# MCU.net
KiCad netlist of a schematic drawn in Altium Designer
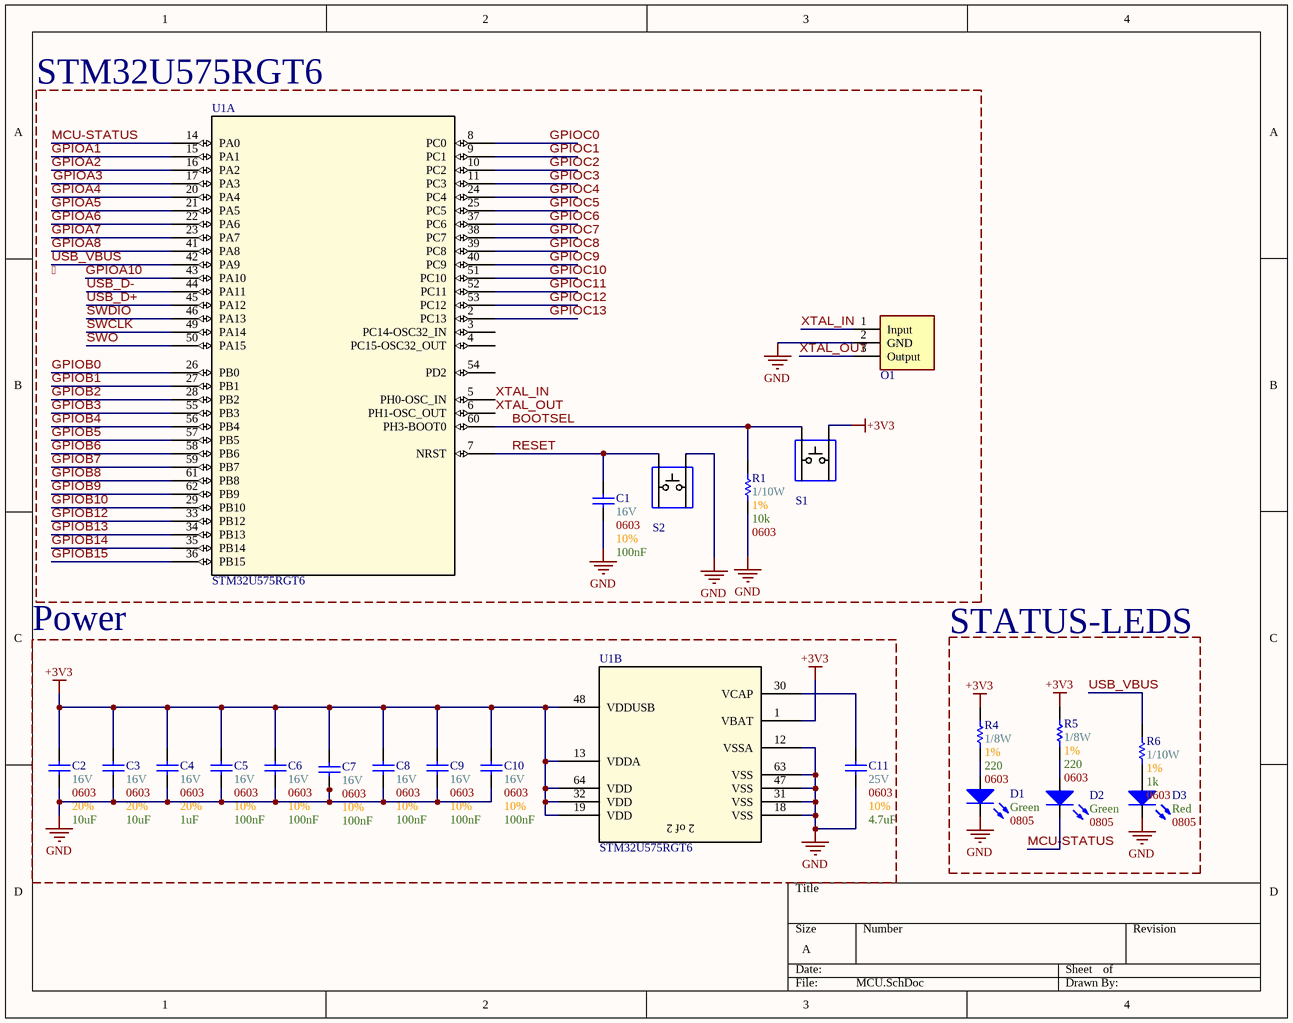
[diagram p0: MCU.SchDoc]

(export (version "E")
  (design (tool "Eeschema 10.0.6"))
  (components
    (comp (ref "C1")
      (value "[Cap] 0603 0.1uF 10% 16V")
      (footprint "[Cap] SMD 0603")
      (description "CC0603KRX7R7BB104")
      (fields
        (field (name "MAX VOLTAGE") "16V")
        (field (name "SIZE PACKAGE") "0603")
        (field (name "TOLERANCE") "10%")
        (field (name "CAPACITANCE") "100nF")
      )
      (libsource (lib "Capacitors") (part "[Cap] 0603 0.1uF 10% 16V"))
    )
    (comp (ref "C2")
      (value "[Cap] 0603 10uF 20% 16V")
      (footprint "[Cap] SMD 0603")
      (description "GRM188C81C106MA73D")
      (fields
        (field (name "MAX VOLTAGE") "16V")
        (field (name "SIZE PACKAGE") "0603")
        (field (name "TOLERANCE") "20%")
        (field (name "CAPACITANCE") "10uF")
      )
      (libsource (lib "Capacitors") (part "[Cap] 0603 10uF 20% 16V"))
    )
    (comp (ref "C3")
      (value "[Cap] 0603 10uF 20% 16V")
      (footprint "[Cap] SMD 0603")
      (description "GRM188C81C106MA73D")
      (fields
        (field (name "MAX VOLTAGE") "16V")
        (field (name "SIZE PACKAGE") "0603")
        (field (name "TOLERANCE") "20%")
        (field (name "CAPACITANCE") "10uF")
      )
      (libsource (lib "Capacitors") (part "[Cap] 0603 10uF 20% 16V"))
    )
    (comp (ref "C4")
      (value "[Cap] 0603 10uF 20% 16V")
      (footprint "[Cap] SMD 0603")
      (description "GRM188C81C106MA73D")
      (fields
        (field (name "MAX VOLTAGE") "16V")
        (field (name "SIZE PACKAGE") "0603")
        (field (name "TOLERANCE") "20%")
        (field (name "CAPACITANCE") "1uF")
      )
      (libsource (lib "Capacitors") (part "[Cap] 0603 10uF 20% 16V"))
    )
    (comp (ref "C5")
      (value "[Cap] 0603 0.1uF 10% 16V")
      (footprint "[Cap] SMD 0603")
      (description "CC0603KRX7R7BB104")
      (fields
        (field (name "MAX VOLTAGE") "16V")
        (field (name "SIZE PACKAGE") "0603")
        (field (name "TOLERANCE") "10%")
        (field (name "CAPACITANCE") "100nF")
      )
      (libsource (lib "Capacitors") (part "[Cap] 0603 0.1uF 10% 16V"))
    )
    (comp (ref "C6")
      (value "[Cap] 0603 0.1uF 10% 16V")
      (footprint "[Cap] SMD 0603")
      (description "CC0603KRX7R7BB104")
      (fields
        (field (name "MAX VOLTAGE") "16V")
        (field (name "SIZE PACKAGE") "0603")
        (field (name "TOLERANCE") "10%")
        (field (name "CAPACITANCE") "100nF")
      )
      (libsource (lib "Capacitors") (part "[Cap] 0603 0.1uF 10% 16V"))
    )
    (comp (ref "C7")
      (value "[Cap] 0603 0.1uF 10% 16V")
      (footprint "[Cap] SMD 0603")
      (description "CC0603KRX7R7BB104")
      (fields
        (field (name "MAX VOLTAGE") "16V")
        (field (name "SIZE PACKAGE") "0603")
        (field (name "TOLERANCE") "10%")
        (field (name "CAPACITANCE") "100nF")
      )
      (libsource (lib "Capacitors") (part "[Cap] 0603 0.1uF 10% 16V"))
    )
    (comp (ref "C8")
      (value "[Cap] 0603 0.1uF 10% 16V")
      (footprint "[Cap] SMD 0603")
      (description "CC0603KRX7R7BB104")
      (fields
        (field (name "MAX VOLTAGE") "16V")
        (field (name "SIZE PACKAGE") "0603")
        (field (name "TOLERANCE") "10%")
        (field (name "CAPACITANCE") "100nF")
      )
      (libsource (lib "Capacitors") (part "[Cap] 0603 0.1uF 10% 16V"))
    )
    (comp (ref "C9")
      (value "[Cap] 0603 0.1uF 10% 16V")
      (footprint "[Cap] SMD 0603")
      (description "CC0603KRX7R7BB104")
      (fields
        (field (name "MAX VOLTAGE") "16V")
        (field (name "SIZE PACKAGE") "0603")
        (field (name "TOLERANCE") "10%")
        (field (name "CAPACITANCE") "100nF")
      )
      (libsource (lib "Capacitors") (part "[Cap] 0603 0.1uF 10% 16V"))
    )
    (comp (ref "C10")
      (value "[Cap] 0603 0.1uF 10% 16V")
      (footprint "[Cap] SMD 0603")
      (description "CC0603KRX7R7BB104")
      (fields
        (field (name "MAX VOLTAGE") "16V")
        (field (name "SIZE PACKAGE") "0603")
        (field (name "TOLERANCE") "10%")
        (field (name "CAPACITANCE") "100nF")
      )
      (libsource (lib "Capacitors") (part "[Cap] 0603 0.1uF 10% 16V"))
    )
    (comp (ref "C11")
      (value "[Cap] 0603 4.7uF 10% 25V")
      (footprint "[Cap] SMD 0603")
      (description "GRM188R61E475KE11D")
      (fields
        (field (name "MAX VOLTAGE") "25V")
        (field (name "SIZE PACKAGE") "0603")
        (field (name "TOLERANCE") "10%")
        (field (name "CAPACITANCE") "4.7uF")
      )
      (libsource (lib "Capacitors") (part "[Cap] 0603 4.7uF 10% 25V"))
    )
    (comp (ref "D1")
      (value "[LED] SMD 0805 Green")
      (footprint "[LED] SMD 0805")
      (description "LG R971-KN-1-0-20-R18")
      (fields (field (name "COLOR") "Green") (field (name "SIZE PACKAGE") "0805"))
      (libsource (lib "LEDs") (part "[LED] SMD 0805 Green"))
    )
    (comp (ref "D2")
      (value "[LED] SMD 0805 Green")
      (footprint "[LED] SMD 0805")
      (description "LG R971-KN-1-0-20-R18")
      (fields (field (name "COLOR") "Green") (field (name "SIZE PACKAGE") "0805"))
      (libsource (lib "LEDs") (part "[LED] SMD 0805 Green"))
    )
    (comp (ref "D3")
      (value "[LED] SMD 0805 Red")
      (footprint "[LED] SMD 0805")
      (description "LS R976-NR-1-0-20-R18")
      (fields (field (name "COLOR") "Red") (field (name "SIZE PACKAGE") "0805"))
      (libsource (lib "LEDs") (part "[LED] SMD 0805 Red"))
    )
    (comp (ref "O1")
      (value "XOSC 12MHz")
      (footprint "[Resonator] SMD 12MHz")
      (description "CSTNE12M0GH5L000R0")
      (libsource (lib "Crystals and Oscillators") (part "[Resonator] SMD 12MHz"))
    )
    (comp (ref "R1")
      (value "[10k] SMD 0603 1% 1/8W")
      (footprint "[Res] SMD 0603")
      (description "RMCF0603FT10K0")
      (fields
        (field (name "WATTAGE") "1/10W")
        (field (name "TOLERANCE") "1%")
        (field (name "RESISTANCE") "10k")
        (field (name "SIZE PACKAGE") "0603")
      )
      (libsource (lib "Resistors") (part "[10k] SMD 0603 1% 1/8W"))
    )
    (comp (ref "R4")
      (value "[220] SMD 0603 1% 1/10W")
      (footprint "[Res] SMD 0603")
      (description "CRGCQ0805F220R")
      (fields
        (field (name "WATTAGE") "1/8W")
        (field (name "TOLERANCE") "1%")
        (field (name "RESISTANCE") "220")
        (field (name "SIZE PACKAGE") "0603")
      )
      (libsource (lib "Resistors") (part "[220] SMD 0603 1% 1/10W"))
    )
    (comp (ref "R5")
      (value "[220] SMD 0603 1% 1/10W")
      (footprint "[Res] SMD 0603")
      (description "CRGCQ0805F220R")
      (fields
        (field (name "WATTAGE") "1/8W")
        (field (name "TOLERANCE") "1%")
        (field (name "RESISTANCE") "220")
        (field (name "SIZE PACKAGE") "0603")
      )
      (libsource (lib "Resistors") (part "[220] SMD 0603 1% 1/10W"))
    )
    (comp (ref "R6")
      (value "[1k] SMD 0603 1% 1/10W")
      (footprint "[Res] SMD 0603")
      (description "RMCF0603FT1K00")
      (fields
        (field (name "WATTAGE") "1/10W")
        (field (name "TOLERANCE") "1%")
        (field (name "RESISTANCE") "1k")
        (field (name "SIZE PACKAGE") "0603")
      )
      (libsource (lib "Resistors") (part "[1k] SMD 0603 1% 1/10W"))
    )
    (comp (ref "S1")
      (value "Standard pushbutton")
      (footprint "[SPST] Pushbutton")
      (libsource (lib "Switches") (part "[SPST] Pushbutton"))
    )
    (comp (ref "S2")
      (value "Standard pushbutton")
      (footprint "[SPST] Pushbutton")
      (libsource (lib "Switches") (part "[SPST] Pushbutton"))
    )
    (comp (ref "U1")
      (value "STM32U575RGT6")
      (footprint "LQFP64-10x10mm_STM")
      (description "Ultra-low-power with FPU Arm Cortex-M33 MCU with TrustZone, 160 MHz with 1 Mbyte of Flash memory")
      (fields (field (name "COPYRIGHT") "Copyright (C) 2025 Ultra Librarian. All rights reserved."))
      (libsource (lib "Solar Gators") (part "STM32U575RGT6"))
    )
  )
  (nets
    (net (code "1") (name "+3V3") (class "Default")
      (node (ref "C10") (pin "2") (pinfunction "2_2") (pintype "passive"))
      (node (ref "C2") (pin "2") (pinfunction "2_2") (pintype "passive"))
      (node (ref "C3") (pin "2") (pinfunction "2_2") (pintype "passive"))
      (node (ref "C4") (pin "2") (pinfunction "2_2") (pintype "passive"))
      (node (ref "C5") (pin "2") (pinfunction "2_2") (pintype "passive"))
      (node (ref "C6") (pin "2") (pinfunction "2_2") (pintype "passive"))
      (node (ref "C7") (pin "2") (pinfunction "2_2") (pintype "passive"))
      (node (ref "C8") (pin "2") (pinfunction "2_2") (pintype "passive"))
      (node (ref "C9") (pin "2") (pinfunction "2_2") (pintype "passive"))
      (node (ref "R4") (pin "2") (pinfunction "2_2") (pintype "passive"))
      (node (ref "R5") (pin "2") (pinfunction "2_2") (pintype "passive"))
      (node (ref "S1") (pin "1") (pintype "power_in"))
      (node (ref "U1") (pin "1") (pinfunction "VBAT_1") (pintype "power_in"))
      (node (ref "U1") (pin "13") (pinfunction "VDDA_13") (pintype "power_in"))
      (node (ref "U1") (pin "19") (pinfunction "VDD_19") (pintype "power_in"))
      (node (ref "U1") (pin "32") (pinfunction "VDD_32") (pintype "power_in"))
      (node (ref "U1") (pin "48") (pinfunction "VDDUSB_48") (pintype "power_in"))
      (node (ref "U1") (pin "64") (pinfunction "VDD_64") (pintype "power_in"))
    )
    (net (code "3") (name "/BOOTSEL") (class "Default")
      (node (ref "R1") (pin "2") (pinfunction "2_2") (pintype "passive"))
      (node (ref "S1") (pin "2") (pintype "power_in"))
      (node (ref "U1") (pin "60") (pinfunction "PH3-BOOT0_60") (pintype "bidirectional"))
    )
    (net (code "4") (name "/GPIOA1") (class "Default")
      (node (ref "U1") (pin "15") (pinfunction "PA1_15") (pintype "bidirectional"))
    )
    (net (code "5") (name "/GPIOA2") (class "Default")
      (node (ref "U1") (pin "16") (pinfunction "PA2_16") (pintype "bidirectional"))
    )
    (net (code "6") (name "/GPIOA3") (class "Default")
      (node (ref "U1") (pin "17") (pinfunction "PA3_17") (pintype "bidirectional"))
    )
    (net (code "7") (name "/GPIOA4") (class "Default")
      (node (ref "U1") (pin "20") (pinfunction "PA4_20") (pintype "bidirectional"))
    )
    (net (code "8") (name "/GPIOA5") (class "Default")
      (node (ref "U1") (pin "21") (pinfunction "PA5_21") (pintype "bidirectional"))
    )
    (net (code "9") (name "/GPIOA6") (class "Default")
      (node (ref "U1") (pin "22") (pinfunction "PA6_22") (pintype "bidirectional"))
    )
    (net (code "10") (name "/GPIOA7") (class "Default")
      (node (ref "U1") (pin "23") (pinfunction "PA7_23") (pintype "bidirectional"))
    )
    (net (code "11") (name "/GPIOA8") (class "Default")
      (node (ref "U1") (pin "41") (pinfunction "PA8_41") (pintype "bidirectional"))
    )
    (net (code "12") (name "/GPIOA10") (class "Default")
      (node (ref "U1") (pin "43") (pinfunction "PA10_43") (pintype "bidirectional"))
    )
    (net (code "13") (name "/GPIOB0") (class "Default")
      (node (ref "U1") (pin "26") (pinfunction "PB0_26") (pintype "bidirectional"))
    )
    (net (code "14") (name "/GPIOB1") (class "Default")
      (node (ref "U1") (pin "27") (pinfunction "PB1_27") (pintype "bidirectional"))
    )
    (net (code "15") (name "/GPIOB2") (class "Default")
      (node (ref "U1") (pin "28") (pinfunction "PB2_28") (pintype "bidirectional"))
    )
    (net (code "16") (name "/GPIOB3") (class "Default")
      (node (ref "U1") (pin "55") (pinfunction "PB3_55") (pintype "bidirectional"))
    )
    (net (code "17") (name "/GPIOB4") (class "Default")
      (node (ref "U1") (pin "56") (pinfunction "PB4_56") (pintype "bidirectional"))
    )
    (net (code "18") (name "/GPIOB5") (class "Default")
      (node (ref "U1") (pin "57") (pinfunction "PB5_57") (pintype "bidirectional"))
    )
    (net (code "19") (name "/GPIOB6") (class "Default")
      (node (ref "U1") (pin "58") (pinfunction "PB6_58") (pintype "bidirectional"))
    )
    (net (code "20") (name "/GPIOB7") (class "Default")
      (node (ref "U1") (pin "59") (pinfunction "PB7_59") (pintype "bidirectional"))
    )
    (net (code "21") (name "/GPIOB8") (class "Default")
      (node (ref "U1") (pin "61") (pinfunction "PB8_61") (pintype "bidirectional"))
    )
    (net (code "22") (name "/GPIOB9") (class "Default")
      (node (ref "U1") (pin "62") (pinfunction "PB9_62") (pintype "bidirectional"))
    )
    (net (code "23") (name "/GPIOB10") (class "Default")
      (node (ref "U1") (pin "29") (pinfunction "PB10_29") (pintype "bidirectional"))
    )
    (net (code "24") (name "/GPIOB12") (class "Default")
      (node (ref "U1") (pin "33") (pinfunction "PB12_33") (pintype "bidirectional"))
    )
    (net (code "25") (name "/GPIOB13") (class "Default")
      (node (ref "U1") (pin "34") (pinfunction "PB13_34") (pintype "bidirectional"))
    )
    (net (code "26") (name "/GPIOB14") (class "Default")
      (node (ref "U1") (pin "35") (pinfunction "PB14_35") (pintype "bidirectional"))
    )
    (net (code "27") (name "/GPIOB15") (class "Default")
      (node (ref "U1") (pin "36") (pinfunction "PB15_36") (pintype "bidirectional"))
    )
    (net (code "28") (name "/GPIOC0") (class "Default")
      (node (ref "U1") (pin "8") (pinfunction "PC0_8") (pintype "bidirectional"))
    )
    (net (code "29") (name "/GPIOC1") (class "Default")
      (node (ref "U1") (pin "9") (pinfunction "PC1_9") (pintype "bidirectional"))
    )
    (net (code "30") (name "/GPIOC2") (class "Default")
      (node (ref "U1") (pin "10") (pinfunction "PC2_10") (pintype "bidirectional"))
    )
    (net (code "31") (name "/GPIOC3") (class "Default")
      (node (ref "U1") (pin "11") (pinfunction "PC3_11") (pintype "bidirectional"))
    )
    (net (code "32") (name "/GPIOC4") (class "Default")
      (node (ref "U1") (pin "24") (pinfunction "PC4_24") (pintype "bidirectional"))
    )
    (net (code "33") (name "/GPIOC5") (class "Default")
      (node (ref "U1") (pin "25") (pinfunction "PC5_25") (pintype "bidirectional"))
    )
    (net (code "34") (name "/GPIOC6") (class "Default")
      (node (ref "U1") (pin "37") (pinfunction "PC6_37") (pintype "bidirectional"))
    )
    (net (code "35") (name "/GPIOC7") (class "Default")
      (node (ref "U1") (pin "38") (pinfunction "PC7_38") (pintype "bidirectional"))
    )
    (net (code "36") (name "/GPIOC8") (class "Default")
      (node (ref "U1") (pin "39") (pinfunction "PC8_39") (pintype "bidirectional"))
    )
    (net (code "37") (name "/GPIOC9") (class "Default")
      (node (ref "U1") (pin "40") (pinfunction "PC9_40") (pintype "bidirectional"))
    )
    (net (code "38") (name "/GPIOC10") (class "Default")
      (node (ref "U1") (pin "51") (pinfunction "PC10_51") (pintype "bidirectional"))
    )
    (net (code "39") (name "/GPIOC11") (class "Default")
      (node (ref "U1") (pin "52") (pinfunction "PC11_52") (pintype "bidirectional"))
    )
    (net (code "40") (name "/GPIOC12") (class "Default")
      (node (ref "U1") (pin "53") (pinfunction "PC12_53") (pintype "bidirectional"))
    )
    (net (code "41") (name "/GPIOC13") (class "Default")
      (node (ref "U1") (pin "2") (pinfunction "PC13_2") (pintype "bidirectional"))
    )
    (net (code "42") (name "/MCU-STATUS") (class "Default")
      (node (ref "D2") (pin "2") (pinfunction "Cathode_2") (pintype "passive"))
      (node (ref "U1") (pin "14") (pinfunction "PA0_14") (pintype "bidirectional"))
    )
    (net (code "43") (name "/RESET") (class "Default")
      (node (ref "C1") (pin "2") (pinfunction "2_2") (pintype "passive"))
      (node (ref "S2") (pin "2") (pintype "power_in"))
      (node (ref "U1") (pin "7") (pinfunction "NRST_7") (pintype "bidirectional"))
    )
    (net (code "44") (name "/SWCLK") (class "Default")
      (node (ref "U1") (pin "49") (pinfunction "PA14_49") (pintype "bidirectional"))
    )
    (net (code "45") (name "/SWDIO") (class "Default")
      (node (ref "U1") (pin "46") (pinfunction "PA13_46") (pintype "bidirectional"))
    )
    (net (code "46") (name "/SWO") (class "Default")
      (node (ref "U1") (pin "50") (pinfunction "PA15_50") (pintype "bidirectional"))
    )
    (net (code "47") (name "/USB_D+") (class "Default")
      (node (ref "U1") (pin "45") (pinfunction "PA12_45") (pintype "bidirectional"))
    )
    (net (code "48") (name "/USB_D-") (class "Default")
      (node (ref "U1") (pin "44") (pinfunction "PA11_44") (pintype "bidirectional"))
    )
    (net (code "49") (name "/USB_VBUS") (class "Default")
      (node (ref "R6") (pin "2") (pinfunction "2_2") (pintype "passive"))
      (node (ref "U1") (pin "42") (pinfunction "PA9_42") (pintype "bidirectional"))
    )
    (net (code "50") (name "/XTAL_IN") (class "Default")
      (node (ref "O1") (pin "1") (pinfunction "Input_1") (pintype "passive"))
      (node (ref "U1") (pin "5") (pinfunction "PH0-OSC_IN_5") (pintype "bidirectional"))
    )
    (net (code "51") (name "/XTAL_OUT") (class "Default")
      (node (ref "O1") (pin "3") (pinfunction "Output_3") (pintype "passive"))
      (node (ref "U1") (pin "6") (pinfunction "PH1-OSC_OUT_6") (pintype "bidirectional"))
    )
    (net (code "52") (name "GND") (class "Default")
      (node (ref "C1") (pin "1") (pinfunction "1_1") (pintype "passive"))
      (node (ref "C10") (pin "1") (pinfunction "1_1") (pintype "passive"))
      (node (ref "C11") (pin "1") (pinfunction "1_1") (pintype "passive"))
      (node (ref "C2") (pin "1") (pinfunction "1_1") (pintype "passive"))
      (node (ref "C3") (pin "1") (pinfunction "1_1") (pintype "passive"))
      (node (ref "C4") (pin "1") (pinfunction "1_1") (pintype "passive"))
      (node (ref "C5") (pin "1") (pinfunction "1_1") (pintype "passive"))
      (node (ref "C6") (pin "1") (pinfunction "1_1") (pintype "passive"))
      (node (ref "C7") (pin "1") (pinfunction "1_1") (pintype "passive"))
      (node (ref "C8") (pin "1") (pinfunction "1_1") (pintype "passive"))
      (node (ref "C9") (pin "1") (pinfunction "1_1") (pintype "passive"))
      (node (ref "D1") (pin "2") (pinfunction "Cathode_2") (pintype "passive"))
      (node (ref "D3") (pin "2") (pinfunction "Cathode_2") (pintype "passive"))
      (node (ref "O1") (pin "2") (pinfunction "GND_2") (pintype "passive"))
      (node (ref "R1") (pin "1") (pinfunction "1_1") (pintype "passive"))
      (node (ref "S2") (pin "1") (pintype "power_in"))
      (node (ref "U1") (pin "12") (pinfunction "VSSA_12") (pintype "power_in"))
      (node (ref "U1") (pin "18") (pinfunction "VSS_18") (pintype "power_in"))
      (node (ref "U1") (pin "31") (pinfunction "VSS_31") (pintype "power_in"))
      (node (ref "U1") (pin "47") (pinfunction "VSS_47") (pintype "power_in"))
      (node (ref "U1") (pin "63") (pinfunction "VSS_63") (pintype "power_in"))
    )
    (net (code "53") (name "Net-(D1-Anode)") (class "Default")
      (node (ref "D1") (pin "1") (pinfunction "Anode_1") (pintype "passive"))
      (node (ref "R4") (pin "1") (pinfunction "1_1") (pintype "passive"))
    )
    (net (code "54") (name "Net-(D2-Anode)") (class "Default")
      (node (ref "D2") (pin "1") (pinfunction "Anode_1") (pintype "passive"))
      (node (ref "R5") (pin "1") (pinfunction "1_1") (pintype "passive"))
    )
    (net (code "55") (name "Net-(D3-Anode)") (class "Default")
      (node (ref "D3") (pin "1") (pinfunction "Anode_1") (pintype "passive"))
      (node (ref "R6") (pin "1") (pinfunction "1_1") (pintype "passive"))
    )
    (net (code "56") (name "Net-(U1B-VCAP)") (class "Default")
      (node (ref "C11") (pin "2") (pinfunction "2_2") (pintype "passive"))
      (node (ref "U1") (pin "30") (pinfunction "VCAP_30") (pintype "power_in"))
    )
    (net (code "57") (name "unconnected-(U1A-PC14-OSC32_IN-Pad3)") (class "Default")
      (node (ref "U1") (pin "3") (pinfunction "PC14-OSC32_IN_3") (pintype "bidirectional"))
    )
    (net (code "58") (name "unconnected-(U1A-PC15-OSC32_OUT-Pad4)") (class "Default")
      (node (ref "U1") (pin "4") (pinfunction "PC15-OSC32_OUT_4") (pintype "bidirectional"))
    )
    (net (code "59") (name "unconnected-(U1A-PD2-Pad54)") (class "Default")
      (node (ref "U1") (pin "54") (pinfunction "PD2_54") (pintype "bidirectional"))
    )
  )
)
